# main_esp.net
KiCad netlist of a schematic drawn in Altium Designer
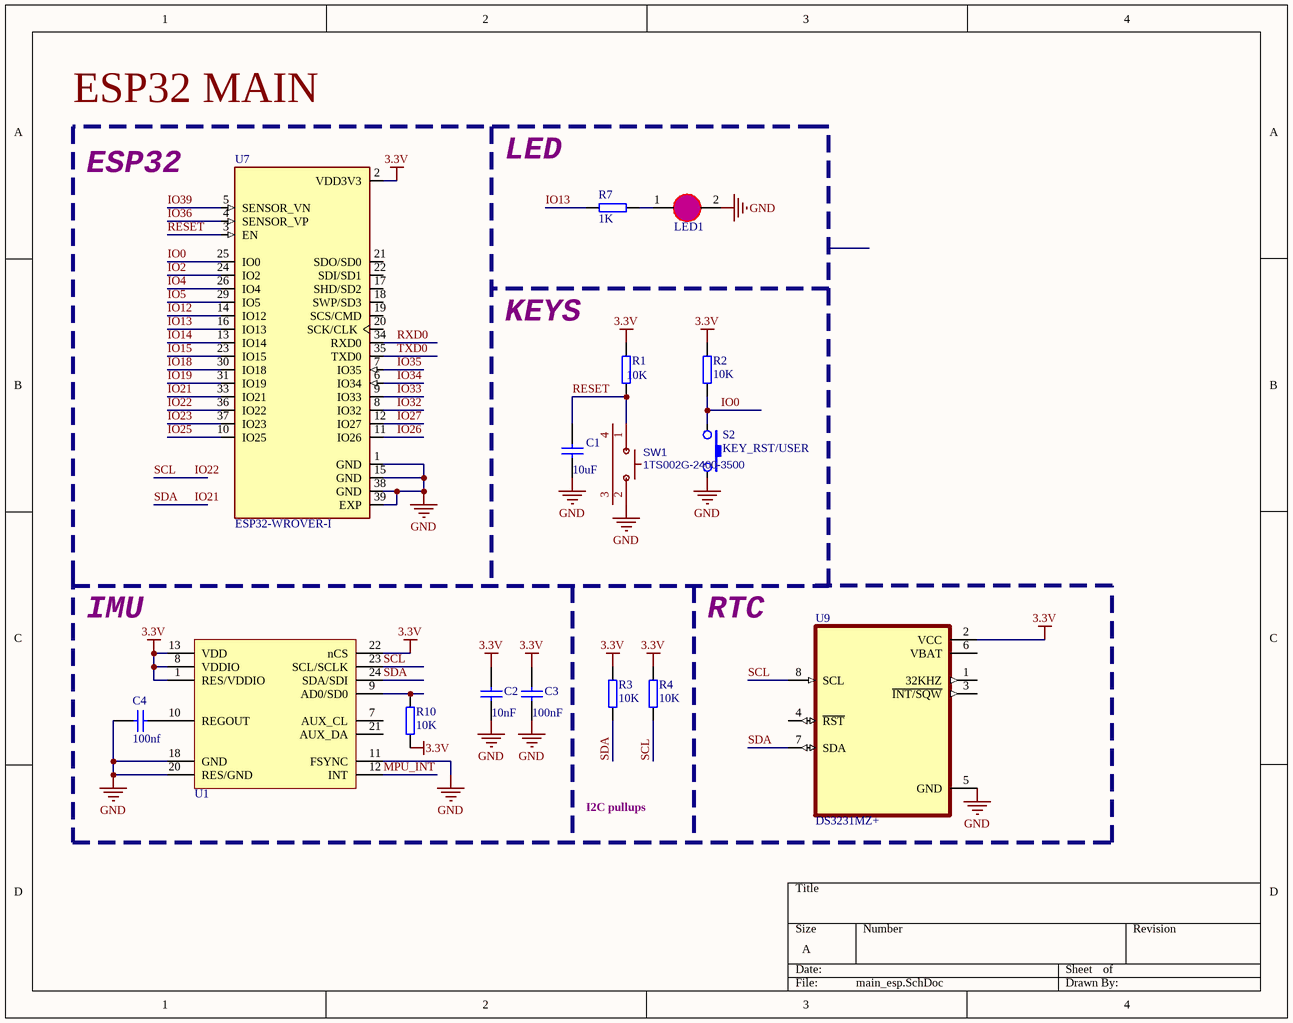
[diagram p0: main_esp.SchDoc]

(export (version "E")
  (design (tool "Eeschema 10.0.6"))
  (components
    (comp (ref "C1")
      (value "10uF")
      (footprint "SMT0603")
      (description "CAP SM 0603 X5R 10uF 10%")
      (fields (field (name "TOLERANCE") "±10%") (field (name "Comment") "Cap Semi"))
      (libsource (lib "electronpowered") (part "CAP-SM-0603-X5R-10uF"))
    )
    (comp (ref "C2")
      (value "10nF")
      (footprint "SMT0603")
      (description "CAP SM 0603 X5R 10uF 10%")
      (fields (field (name "TOLERANCE") "±10%") (field (name "Comment") "Cap Semi"))
      (libsource (lib "electronpowered") (part "CAP-SM-0603-X5R-10uF"))
    )
    (comp (ref "C3")
      (value "100nF")
      (footprint "SMT0603")
      (description "CAP SM 0603 X7R 100nF 10%")
      (fields (field (name "TOLERANCE") "±10%") (field (name "Comment") "Cap Semi"))
      (libsource (lib "electronpowered") (part "CAP-SM-0603-X7R-100nF"))
    )
    (comp (ref "C4")
      (value "100nf")
      (footprint "SMT0603")
      (description "CAP SM 0603 X5R 10uF 10%")
      (fields (field (name "TOLERANCE") "±10%") (field (name "Comment") "Cap Semi"))
      (libsource (lib "electronpowered") (part "CAP-SM-0603-X5R-10uF"))
    )
    (comp (ref "LED1")
      (value "LED3")
      (footprint "LED0805")
      (description "LED SMD 0805")
      (libsource (lib "My Library") (part "LED0805"))
    )
    (comp (ref "R1")
      (value "10K")
      (footprint "SMT0603")
      (description "RES SM 0603 10K")
      (fields (field (name "Comment") "Resistor"))
      (libsource (lib "electronpowered") (part "RES-SM-0603-10K"))
    )
    (comp (ref "R2")
      (value "10K")
      (footprint "SMT0603")
      (description "RES SM 0603 10K")
      (fields (field (name "Comment") "Resistor"))
      (libsource (lib "electronpowered") (part "RES-SM-0603-10K"))
    )
    (comp (ref "R3")
      (value "10K")
      (footprint "SMT0603")
      (description "RES SM 0603 10K")
      (fields (field (name "Comment") "Resistor"))
      (libsource (lib "electronpowered") (part "RES-SM-0603-10K"))
    )
    (comp (ref "R4")
      (value "10K")
      (footprint "SMT0603")
      (description "RES SM 0603 10K")
      (fields (field (name "Comment") "Resistor"))
      (libsource (lib "electronpowered") (part "RES-SM-0603-10K"))
    )
    (comp (ref "R7")
      (value "1K")
      (footprint "SMT0603")
      (description "RES SM 0603 1K")
      (fields (field (name "Comment") "Resistor"))
      (libsource (lib "electronpowered") (part "RES-SM-0603-1K"))
    )
    (comp (ref "R10")
      (value "10K")
      (footprint "SMT0603")
      (description "RES SM 0603 10K")
      (fields (field (name "Comment") "Resistor"))
      (libsource (lib "electronpowered") (part "RES-SM-0603-10K"))
    )
    (comp (ref "S2")
      (value "KEY_RST/USER")
      (footprint "SMT_SW_PTS_820")
      (description "SMT Tactile ‎Switch PTS 820 Series")
      (libsource (lib "NODEMCU_DEVKIT_V1.0") (part "SMT_SW_PTS_820"))
    )
    (comp (ref "SW1")
      (value "1TS002G-2400-3500")
      (footprint "KEY-SMD_1TS002G")
      (fields (field (name "BOM_SUPPLIER PART") "C319378") (field (name "CONTRIBUTOR") "LCSC"))
      (libsource (lib "SW") (part "1TS002G-2400-3500"))
    )
    (comp (ref "U1")
      (value "MPU-9250")
      (footprint "QFN40P300X300X105_HS-25L")
      (libsource (lib "MPU-9250") (part "MPU-9250"))
    )
    (comp (ref "U7")
      (value "ESP32-WROVER-I")
      (footprint "SnapEDApcb:XCVR_ESP32-WROVER-I")
      (fields (field (name "MF") "Espressif Systems"))
      (libsource (lib "SnapEDAsch") (part "ESP32-WROVER-I"))
    )
    (comp (ref "U9")
      (value "DS3231MZ+")
      (footprint "SOIC127P600X175-8N")
      (description "Real Time Clock _RTC_ IC Clock/Calendar IÂ²C, 2-Wire Serial 8-SOIC _0.154, 3.90mm Width_")
      (fields (field (name "MP") "DS3231MZ") (field (name "MF") "Maxim Integrated"))
      (libsource (lib "DS3231MZ_") (part "DS3231MZ+"))
    )
  )
  (nets
    (net (code "1") (name "/IO0") (class "Default")
      (node (ref "R2") (pin "1") (pinfunction "1_1") (pintype "passive"))
      (node (ref "S2") (pin "1") (pinfunction "1_1") (pintype "passive"))
      (node (ref "U7") (pin "25") (pinfunction "IO0_25") (pintype "bidirectional"))
    )
    (net (code "2") (name "/IO2") (class "Default")
      (node (ref "U7") (pin "24") (pinfunction "IO2_24") (pintype "bidirectional"))
    )
    (net (code "3") (name "/IO4") (class "Default")
      (node (ref "U7") (pin "26") (pinfunction "IO4_26") (pintype "bidirectional"))
    )
    (net (code "4") (name "/IO5") (class "Default")
      (node (ref "U7") (pin "29") (pinfunction "IO5_29") (pintype "bidirectional"))
    )
    (net (code "5") (name "/IO12") (class "Default")
      (node (ref "U7") (pin "14") (pinfunction "IO12_14") (pintype "bidirectional"))
    )
    (net (code "6") (name "/IO13") (class "Default")
      (node (ref "R7") (pin "1") (pinfunction "1_1") (pintype "passive"))
      (node (ref "U7") (pin "16") (pinfunction "IO13_16") (pintype "bidirectional"))
    )
    (net (code "7") (name "/IO14") (class "Default")
      (node (ref "U7") (pin "13") (pinfunction "IO14_13") (pintype "bidirectional"))
    )
    (net (code "8") (name "/IO15") (class "Default")
      (node (ref "U7") (pin "23") (pinfunction "IO15_23") (pintype "bidirectional"))
    )
    (net (code "9") (name "/IO18") (class "Default")
      (node (ref "U7") (pin "30") (pinfunction "IO18_30") (pintype "bidirectional"))
    )
    (net (code "10") (name "/IO19") (class "Default")
      (node (ref "U7") (pin "31") (pinfunction "IO19_31") (pintype "bidirectional"))
    )
    (net (code "11") (name "/IO21") (class "Default")
      (node (ref "R3") (pin "1") (pinfunction "1_1") (pintype "passive"))
      (node (ref "U1") (pin "24") (pinfunction "SDA/SDI_24") (pintype "passive"))
      (node (ref "U7") (pin "33") (pinfunction "IO21_33") (pintype "bidirectional"))
      (node (ref "U9") (pin "7") (pinfunction "SDA_7") (pintype "bidirectional"))
    )
    (net (code "12") (name "/IO22") (class "Default")
      (node (ref "R4") (pin "1") (pinfunction "1_1") (pintype "passive"))
      (node (ref "U1") (pin "23") (pinfunction "SCL/SCLK_23") (pintype "passive"))
      (node (ref "U7") (pin "36") (pinfunction "IO22_36") (pintype "bidirectional"))
      (node (ref "U9") (pin "8") (pinfunction "SCL_8") (pintype "input"))
    )
    (net (code "13") (name "/IO23") (class "Default")
      (node (ref "U7") (pin "37") (pinfunction "IO23_37") (pintype "bidirectional"))
    )
    (net (code "14") (name "/IO25") (class "Default")
      (node (ref "U7") (pin "10") (pinfunction "IO25_10") (pintype "bidirectional"))
    )
    (net (code "15") (name "/IO26") (class "Default")
      (node (ref "U7") (pin "11") (pinfunction "IO26_11") (pintype "bidirectional"))
    )
    (net (code "16") (name "/IO27") (class "Default")
      (node (ref "U7") (pin "12") (pinfunction "IO27_12") (pintype "bidirectional"))
    )
    (net (code "17") (name "/IO32") (class "Default")
      (node (ref "U7") (pin "8") (pinfunction "IO32_8") (pintype "bidirectional"))
    )
    (net (code "18") (name "/IO33") (class "Default")
      (node (ref "U7") (pin "9") (pinfunction "IO33_9") (pintype "bidirectional"))
    )
    (net (code "19") (name "/IO34") (class "Default")
      (node (ref "U7") (pin "6") (pinfunction "IO34_6") (pintype "input"))
    )
    (net (code "20") (name "/IO35") (class "Default")
      (node (ref "U7") (pin "7") (pinfunction "IO35_7") (pintype "input"))
    )
    (net (code "21") (name "/IO36") (class "Default")
      (node (ref "U7") (pin "4") (pinfunction "SENSOR_VP_4") (pintype "input"))
    )
    (net (code "22") (name "/IO39") (class "Default")
      (node (ref "U7") (pin "5") (pinfunction "SENSOR_VN_5") (pintype "input"))
    )
    (net (code "23") (name "/MPU_INT") (class "Default")
      (node (ref "U1") (pin "12") (pinfunction "INT_12") (pintype "passive"))
    )
    (net (code "24") (name "/RESET") (class "Default")
      (node (ref "C1") (pin "2") (pinfunction "2_2") (pintype "passive"))
      (node (ref "R1") (pin "1") (pinfunction "1_1") (pintype "passive"))
      (node (ref "SW1") (pin "1") (pinfunction "1_1") (pintype "passive"))
      (node (ref "U7") (pin "3") (pinfunction "EN_3") (pintype "input"))
    )
    (net (code "25") (name "/RXD0") (class "Default")
      (node (ref "U7") (pin "34") (pinfunction "RXD0_34") (pintype "bidirectional"))
    )
    (net (code "26") (name "/TXD0") (class "Default")
      (node (ref "U7") (pin "35") (pinfunction "TXD0_35") (pintype "bidirectional"))
    )
    (net (code "27") (name "3.3V") (class "Default")
      (node (ref "C2") (pin "2") (pinfunction "2_2") (pintype "passive"))
      (node (ref "C3") (pin "2") (pinfunction "2_2") (pintype "passive"))
      (node (ref "R1") (pin "2") (pinfunction "2_2") (pintype "passive"))
      (node (ref "R10") (pin "1") (pinfunction "1_1") (pintype "passive"))
      (node (ref "R2") (pin "2") (pinfunction "2_2") (pintype "passive"))
      (node (ref "R3") (pin "2") (pinfunction "2_2") (pintype "passive"))
      (node (ref "R4") (pin "2") (pinfunction "2_2") (pintype "passive"))
      (node (ref "U1") (pin "1") (pinfunction "RES/VDDIO_1") (pintype "passive"))
      (node (ref "U1") (pin "13") (pinfunction "VDD_13") (pintype "passive"))
      (node (ref "U1") (pin "22") (pinfunction "nCS_22") (pintype "passive"))
      (node (ref "U1") (pin "8") (pinfunction "VDDIO_8") (pintype "passive"))
      (node (ref "U7") (pin "2") (pinfunction "VDD3V3_2") (pintype "power_in"))
      (node (ref "U9") (pin "2") (pinfunction "VCC_2") (pintype "power_in"))
    )
    (net (code "28") (name "GND") (class "Default")
      (node (ref "C1") (pin "1") (pinfunction "1_1") (pintype "passive"))
      (node (ref "C2") (pin "1") (pinfunction "1_1") (pintype "passive"))
      (node (ref "C3") (pin "1") (pinfunction "1_1") (pintype "passive"))
      (node (ref "C4") (pin "2") (pinfunction "2_2") (pintype "passive"))
      (node (ref "LED1") (pin "2") (pinfunction "K_2") (pintype "passive"))
      (node (ref "S2") (pin "2") (pinfunction "2_2") (pintype "passive"))
      (node (ref "SW1") (pin "2") (pinfunction "2_2") (pintype "passive"))
      (node (ref "U1") (pin "11") (pinfunction "FSYNC_11") (pintype "passive"))
      (node (ref "U1") (pin "18") (pinfunction "GND_18") (pintype "passive"))
      (node (ref "U1") (pin "20") (pinfunction "RES/GND_20") (pintype "passive"))
      (node (ref "U7") (pin "1") (pinfunction "GND_1") (pintype "power_in"))
      (node (ref "U7") (pin "15") (pinfunction "GND_15") (pintype "power_in"))
      (node (ref "U7") (pin "38") (pinfunction "GND_38") (pintype "power_in"))
      (node (ref "U7") (pin "39") (pinfunction "EXP_39") (pintype "power_in"))
      (node (ref "U9") (pin "5") (pinfunction "GND_5") (pintype "power_in"))
    )
    (net (code "29") (name "Net-(LED1-A)") (class "Default")
      (node (ref "LED1") (pin "1") (pinfunction "A_1") (pintype "passive"))
      (node (ref "R7") (pin "2") (pinfunction "2_2") (pintype "passive"))
    )
    (net (code "30") (name "Net-(U1-AD0{slash}SD0)") (class "Default")
      (node (ref "R10") (pin "2") (pinfunction "2_2") (pintype "passive"))
      (node (ref "U1") (pin "9") (pinfunction "AD0/SD0_9") (pintype "passive"))
    )
    (net (code "31") (name "Net-(U1-REGOUT)") (class "Default")
      (node (ref "C4") (pin "1") (pinfunction "1_1") (pintype "passive"))
      (node (ref "U1") (pin "10") (pinfunction "REGOUT_10") (pintype "passive"))
    )
    (net (code "32") (name "unconnected-(SW1-Pad3)") (class "Default")
      (node (ref "SW1") (pin "3") (pinfunction "3_3") (pintype "passive"))
    )
    (net (code "33") (name "unconnected-(SW1-Pad4)") (class "Default")
      (node (ref "SW1") (pin "4") (pinfunction "4_4") (pintype "passive"))
    )
    (net (code "34") (name "unconnected-(U1-AUX_CL-Pad7)") (class "Default")
      (node (ref "U1") (pin "7") (pinfunction "AUX_CL_7") (pintype "passive"))
    )
    (net (code "35") (name "unconnected-(U1-AUX_DA-Pad21)") (class "Default")
      (node (ref "U1") (pin "21") (pinfunction "AUX_DA_21") (pintype "passive"))
    )
    (net (code "36") (name "unconnected-(U7-SCK{slash}CLK-Pad20)") (class "Default")
      (node (ref "U7") (pin "20") (pinfunction "SCK/CLK_20") (pintype "bidirectional"))
    )
    (net (code "37") (name "unconnected-(U7-SCS{slash}CMD-Pad19)") (class "Default")
      (node (ref "U7") (pin "19") (pinfunction "SCS/CMD_19") (pintype "bidirectional"))
    )
    (net (code "38") (name "unconnected-(U7-SDI{slash}SD1-Pad22)") (class "Default")
      (node (ref "U7") (pin "22") (pinfunction "SDI/SD1_22") (pintype "bidirectional"))
    )
    (net (code "39") (name "unconnected-(U7-SDO{slash}SD0-Pad21)") (class "Default")
      (node (ref "U7") (pin "21") (pinfunction "SDO/SD0_21") (pintype "bidirectional"))
    )
    (net (code "40") (name "unconnected-(U7-SHD{slash}SD2-Pad17)") (class "Default")
      (node (ref "U7") (pin "17") (pinfunction "SHD/SD2_17") (pintype "bidirectional"))
    )
    (net (code "41") (name "unconnected-(U7-SWP{slash}SD3-Pad18)") (class "Default")
      (node (ref "U7") (pin "18") (pinfunction "SWP/SD3_18") (pintype "bidirectional"))
    )
    (net (code "42") (name "unconnected-(U9-32KHZ-Pad1)") (class "Default")
      (node (ref "U9") (pin "1") (pinfunction "32KHZ_1") (pintype "output"))
    )
    (net (code "43") (name "unconnected-(U9-VBAT-Pad6)") (class "Default")
      (node (ref "U9") (pin "6") (pinfunction "VBAT_6") (pintype "power_in"))
    )
    (net (code "44") (name "unconnected-(U9-~{INT{slash}SQW}-Pad3)") (class "Default")
      (node (ref "U9") (pin "3") (pinfunction "~{INT/SQW}_3") (pintype "output"))
    )
    (net (code "45") (name "unconnected-(U9-~{RST}-Pad4)") (class "Default")
      (node (ref "U9") (pin "4") (pinfunction "~{RST}_4") (pintype "bidirectional"))
    )
  )
)
